# Vs.net
KiCad netlist of a schematic drawn in Altium Designer
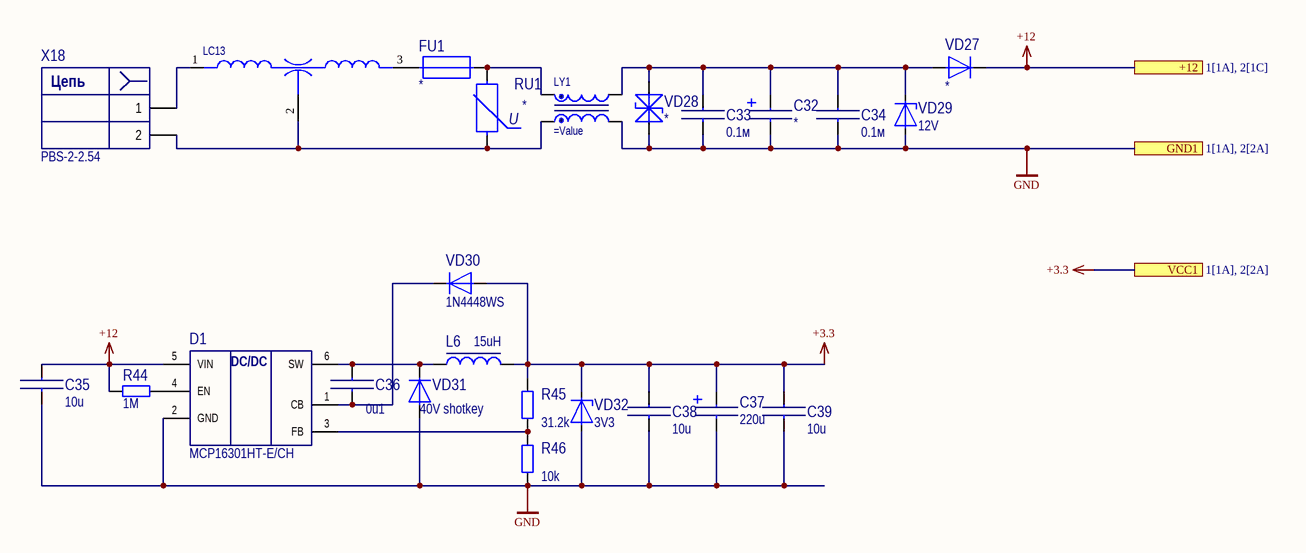
[diagram p0: Vs.SchDoc]

(export (version "E")
  (design (tool "Eeschema 10.0.6"))
  (components
    (comp (ref "C32")
      (value "*")
      (footprint "ECAP 220 50V")
      (description "Конденсатор электролитический")
      (libsource (lib "Schgost") (part "C pol"))
    )
    (comp (ref "C33")
      (value "0.1м")
      (footprint "3216[1206]")
      (description "Конденсатор")
      (fields (field (name "MANUFACTURER") "Murata") (field (name "MANUFACTURERPARTNUMBER") "GRM21_R71H104"))
      (libsource (lib "Schgost") (part "C nonpol"))
    )
    (comp (ref "C34")
      (value "0.1м")
      (footprint "3216[1206]")
      (description "Конденсатор")
      (fields (field (name "MANUFACTURER") "Murata") (field (name "MANUFACTURERPARTNUMBER") "GRM21_R71H104"))
      (libsource (lib "Schgost") (part "C nonpol"))
    )
    (comp (ref "C35")
      (value "10u")
      (footprint "3216[1206]")
      (description "Конденсатор")
      (fields (field (name "MANUFACTURER") "Murata") (field (name "MANUFACTURERPARTNUMBER") "GRM21_R71H104"))
      (libsource (lib "Schgost") (part "C nonpol"))
    )
    (comp (ref "C36")
      (value "0u1")
      (footprint "2012[0805]")
      (description "Конденсатор")
      (fields (field (name "MANUFACTURER") "Murata") (field (name "MANUFACTURERPARTNUMBER") "GRM21_R71H104"))
      (libsource (lib "Schgost") (part "C nonpol"))
    )
    (comp (ref "C37")
      (value "220u")
      (footprint "ECAP 220 50V")
      (description "Конденсатор электролитический")
      (libsource (lib "Schgost") (part "C pol"))
    )
    (comp (ref "C38")
      (value "10u")
      (footprint "6332[2512]")
      (description "Конденсатор")
      (fields (field (name "MANUFACTURER") "Murata") (field (name "MANUFACTURERPARTNUMBER") "GRM21_R71H104"))
      (libsource (lib "Schgost") (part "C nonpol"))
    )
    (comp (ref "C39")
      (value "10u")
      (footprint "6332[2512]")
      (description "Конденсатор")
      (fields (field (name "MANUFACTURER") "Murata") (field (name "MANUFACTURERPARTNUMBER") "GRM21_R71H104"))
      (libsource (lib "Schgost") (part "C nonpol"))
    )
    (comp (ref "D1")
      (value "MCP16301HT-E/CH")
      (footprint "SOT23-6")
      (description "DC/DC regulator")
      (fields (field (name "MANUFACTURER") "Microchip"))
      (libsource (lib "Schlibgost_pn") (part "MCP16301"))
    )
    (comp (ref "FU1")
      (value "*")
      (footprint "2410")
      (description "Вставка плавкая")
      (fields (field (name "MANUFACTURERPARTNUMBER") "ВП1-2"))
      (libsource (lib "Schlibgost") (part "FU"))
    )
    (comp (ref "L6")
      (value "15uH")
      (footprint "IND5750")
      (description "Дроссель")
      (libsource (lib "Schgost") (part "L with core"))
    )
    (comp (ref "LC13")
      (value "~")
      (footprint "NFE61PT102E1H9L")
      (libsource (lib "Schlibgost_pn") (part "Фильтр ЭМП LCL"))
    )
    (comp (ref "LY1")
      (value "~")
      (footprint "B82793S0513N201")
      (libsource (lib "Schgost") (part "Дроссель синфазный"))
    )
    (comp (ref "R44")
      (value "1М")
      (footprint "2012[0805]")
      (description "Резистор")
      (fields (field (name "TOLERANCE") "5%") (field (name "MANUFACTURER") "Yageo"))
      (libsource (lib "") (part "R-4del_1"))
    )
    (comp (ref "R45")
      (value "31.2k")
      (footprint "2012[0805]")
      (description "Резистор")
      (fields (field (name "TOLERANCE") "5%") (field (name "MANUFACTURER") "Yageo"))
      (libsource (lib "Schgost") (part "R-4del"))
    )
    (comp (ref "R46")
      (value "10k")
      (footprint "2012[0805]")
      (description "Резистор")
      (fields (field (name "TOLERANCE") "5%") (field (name "MANUFACTURER") "Yageo"))
      (libsource (lib "Schgost") (part "R-4del"))
    )
    (comp (ref "RU1")
      (value "*")
      (footprint "3225[1210]")
      (description "Варистор")
      (libsource (lib "Schlibgost") (part "RU Varistor"))
    )
    (comp (ref "VD27")
      (value "*")
      (footprint "SMB")
      (description "Диод")
      (libsource (lib "Schgost") (part "VD Diod"))
    )
    (comp (ref "VD28")
      (value "*")
      (footprint "SMС")
      (description "Стабилитрон двусторонний")
      (libsource (lib "Schgost") (part "VD Stabilitron_bidir"))
    )
    (comp (ref "VD29")
      (value "12V")
      (footprint "SMС")
      (description "Стабилитрон односторонний")
      (libsource (lib "Schlibgost") (part "VD Stabilitron"))
    )
    (comp (ref "VD30")
      (value "1N4448WS")
      (footprint "SOD-323")
      (description "Диод")
      (libsource (lib "Schlibgost") (part "VD Diod"))
    )
    (comp (ref "VD31")
      (value "40V shotkey")
      (footprint "SOD-123")
      (description "Диод")
      (libsource (lib "Schlibgost") (part "VD Diod"))
    )
    (comp (ref "VD32")
      (value "3V3")
      (footprint "SOD-80")
      (description "Стабилитрон односторонний")
      (libsource (lib "Schlibgost") (part "VD Stabilitron"))
    )
    (comp (ref "X18")
      (value "PBS-2-2.54")
      (footprint "CWF-2")
      (description "Гнездо 2-контакта")
      (libsource (lib "Schgost") (part "XP-PBS-2"))
    )
  )
  (nets
    (net (code "1") (name "+3.3") (class "Default")
      (node (ref "C37") (pin "1") (pinfunction "1_1") (pintype "passive"))
      (node (ref "C38") (pin "1") (pinfunction "1_1") (pintype "passive"))
      (node (ref "C39") (pin "1") (pinfunction "1_1") (pintype "passive"))
      (node (ref "L6") (pin "2") (pinfunction "2_2") (pintype "passive"))
      (node (ref "R45") (pin "2") (pinfunction "2_2") (pintype "passive"))
      (node (ref "VD30") (pin "1") (pinfunction "A_1") (pintype "passive"))
      (node (ref "VD32") (pin "2") (pinfunction "K_2") (pintype "passive"))
    )
    (net (code "2") (name "+12") (class "Default")
      (node (ref "C35") (pin "1") (pinfunction "1_1") (pintype "passive"))
      (node (ref "D1") (pin "5") (pinfunction "VIN_5") (pintype "passive"))
      (node (ref "R44") (pin "2") (pinfunction "2_2") (pintype "passive"))
      (node (ref "VD27") (pin "2") (pinfunction "K_2") (pintype "passive"))
    )
    (net (code "3") (name "GND") (class "Default")
      (node (ref "C32") (pin "2") (pinfunction "2_2") (pintype "passive"))
      (node (ref "C33") (pin "2") (pinfunction "2_2") (pintype "passive"))
      (node (ref "C34") (pin "2") (pinfunction "2_2") (pintype "passive"))
      (node (ref "C35") (pin "2") (pinfunction "2_2") (pintype "passive"))
      (node (ref "C37") (pin "2") (pinfunction "2_2") (pintype "passive"))
      (node (ref "C38") (pin "2") (pinfunction "2_2") (pintype "passive"))
      (node (ref "C39") (pin "2") (pinfunction "2_2") (pintype "passive"))
      (node (ref "D1") (pin "2") (pinfunction "GND_2") (pintype "passive"))
      (node (ref "LY1") (pin "4") (pinfunction "4_4") (pintype "passive"))
      (node (ref "R46") (pin "1") (pinfunction "1_1") (pintype "passive"))
      (node (ref "VD28") (pin "2") (pinfunction "K_2") (pintype "passive"))
      (node (ref "VD29") (pin "1") (pinfunction "A_1") (pintype "passive"))
      (node (ref "VD31") (pin "1") (pinfunction "A_1") (pintype "passive"))
      (node (ref "VD32") (pin "1") (pinfunction "A_1") (pintype "passive"))
    )
    (net (code "4") (name "Net-(D1-CB)") (class "Default")
      (node (ref "C36") (pin "1") (pinfunction "1_1") (pintype "passive"))
      (node (ref "D1") (pin "1") (pinfunction "CB_1") (pintype "passive"))
      (node (ref "VD30") (pin "2") (pinfunction "K_2") (pintype "passive"))
    )
    (net (code "5") (name "Net-(D1-EN)") (class "Default")
      (node (ref "D1") (pin "4") (pinfunction "EN_4") (pintype "passive"))
      (node (ref "R44") (pin "1") (pinfunction "1_1") (pintype "passive"))
    )
    (net (code "6") (name "Net-(D1-FB)") (class "Default")
      (node (ref "D1") (pin "3") (pinfunction "FB_3") (pintype "passive"))
      (node (ref "R45") (pin "1") (pinfunction "1_1") (pintype "passive"))
      (node (ref "R46") (pin "2") (pinfunction "2_2") (pintype "passive"))
    )
    (net (code "7") (name "Net-(D1-SW)") (class "Default")
      (node (ref "C36") (pin "2") (pinfunction "2_2") (pintype "passive"))
      (node (ref "D1") (pin "6") (pinfunction "SW_6") (pintype "passive"))
      (node (ref "L6") (pin "1") (pinfunction "1_1") (pintype "passive"))
      (node (ref "VD31") (pin "2") (pinfunction "K_2") (pintype "passive"))
    )
    (net (code "8") (name "Net-(FU1-Pad2)") (class "Default")
      (node (ref "FU1") (pin "2") (pinfunction "2_2") (pintype "passive"))
      (node (ref "LY1") (pin "1") (pinfunction "1_1") (pintype "passive"))
      (node (ref "RU1") (pin "2") (pinfunction "2_2") (pintype "passive"))
    )
    (net (code "9") (name "Net-(LC13-GND)") (class "Default")
      (node (ref "LC13") (pin "2") (pinfunction "GND_2") (pintype "passive"))
      (node (ref "LY1") (pin "2") (pinfunction "2_2") (pintype "passive"))
      (node (ref "RU1") (pin "1") (pinfunction "1_1") (pintype "passive"))
      (node (ref "X18") (pin "2") (pinfunction "2_2") (pintype "passive"))
    )
    (net (code "10") (name "Net-(LC13-INPUT)") (class "Default")
      (node (ref "LC13") (pin "1") (pinfunction "INPUT_1") (pintype "passive"))
      (node (ref "X18") (pin "1") (pinfunction "1_1") (pintype "passive"))
    )
    (net (code "11") (name "Net-(LC13-OUTPUT)") (class "Default")
      (node (ref "FU1") (pin "1") (pinfunction "1_1") (pintype "passive"))
      (node (ref "LC13") (pin "3") (pinfunction "OUTPUT_3") (pintype "passive"))
    )
    (net (code "12") (name "Net-(VD27-A)") (class "Default")
      (node (ref "C32") (pin "1") (pinfunction "1_1") (pintype "passive"))
      (node (ref "C33") (pin "1") (pinfunction "1_1") (pintype "passive"))
      (node (ref "C34") (pin "1") (pinfunction "1_1") (pintype "passive"))
      (node (ref "LY1") (pin "3") (pinfunction "3_3") (pintype "passive"))
      (node (ref "VD27") (pin "1") (pinfunction "A_1") (pintype "passive"))
      (node (ref "VD28") (pin "1") (pinfunction "A_1") (pintype "passive"))
      (node (ref "VD29") (pin "2") (pinfunction "K_2") (pintype "passive"))
    )
  )
)
